# cont_board.net
KiCad netlist of a schematic drawn in EAGLE
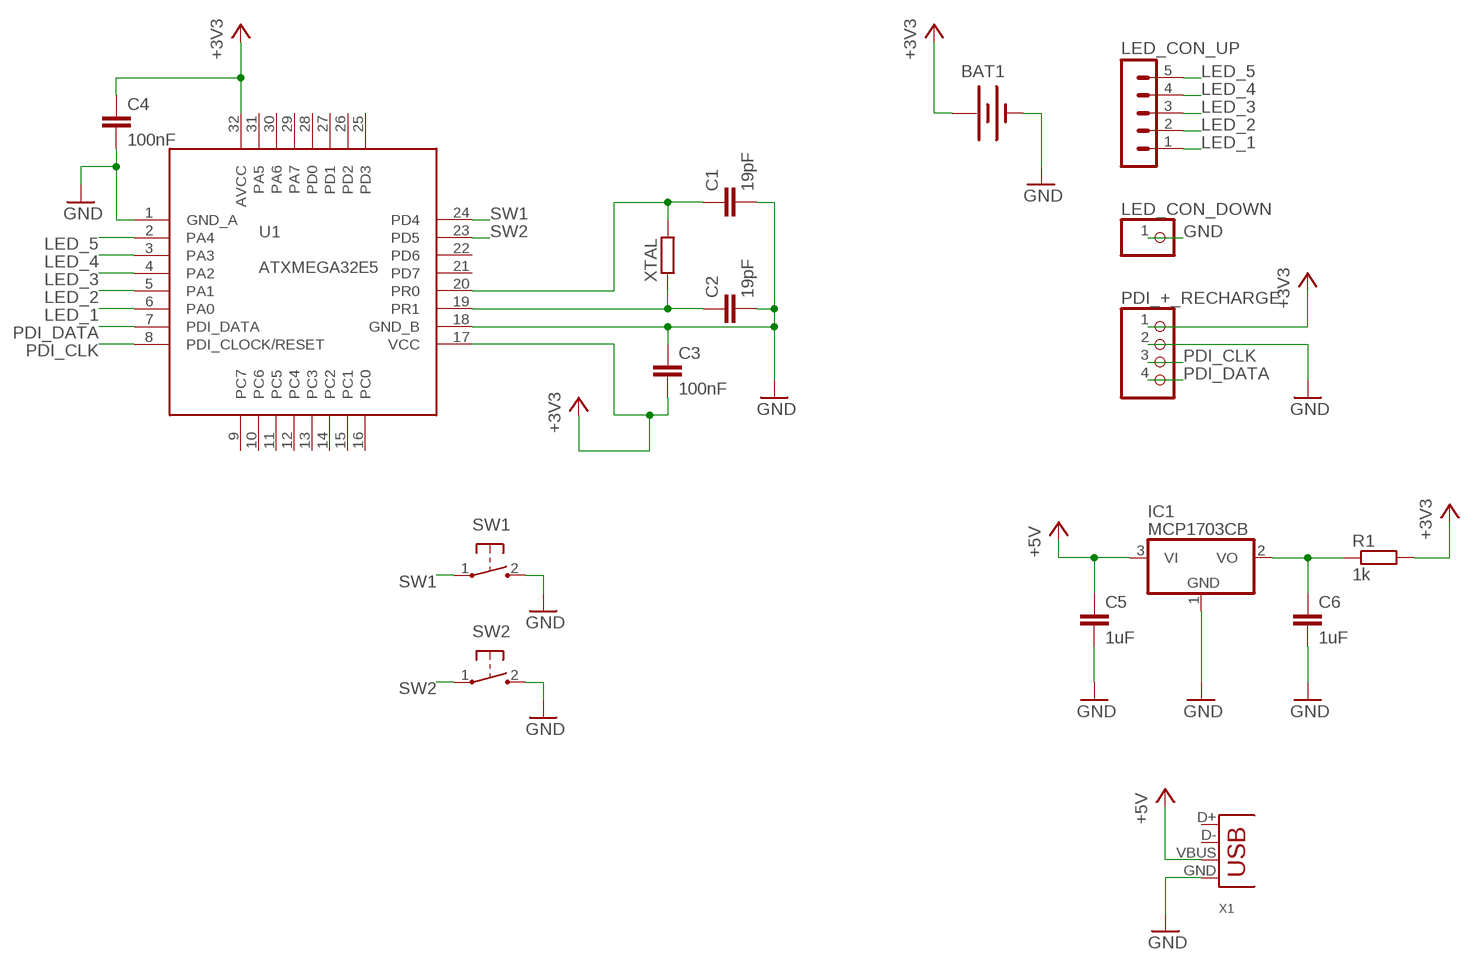
[diagram p0: schematic, sheet 1]

(export (version "E")
  (design (tool "Eeschema 10.0.6"))
  (components
    (comp (ref "BAT1")
      (value "BATTERY12MM")
      (footprint "eagle-import:BATTCON_12MM")
      (libsource (lib "eagle-import") (part "BATTERY12MM"))
    )
    (comp (ref "C1")
      (value "19pF")
      (footprint "eagle-import:C0402")
      (libsource (lib "eagle-import") (part "C-EUC0402"))
    )
    (comp (ref "C2")
      (value "19pF")
      (footprint "eagle-import:C0402")
      (libsource (lib "eagle-import") (part "C-EUC0402"))
    )
    (comp (ref "C3")
      (value "100nF")
      (footprint "eagle-import:C0402")
      (libsource (lib "eagle-import") (part "C-EUC0402"))
    )
    (comp (ref "C4")
      (value "100nF")
      (footprint "eagle-import:C0402")
      (libsource (lib "eagle-import") (part "C-EUC0402"))
    )
    (comp (ref "C5")
      (value "1uF")
      (footprint "eagle-import:C0402")
      (libsource (lib "eagle-import") (part "C-EUC0402"))
    )
    (comp (ref "C6")
      (value "1uF")
      (footprint "eagle-import:C0402")
      (libsource (lib "eagle-import") (part "C-EUC0402"))
    )
    (comp (ref "IC1")
      (value "MCP1703CB")
      (footprint "eagle-import:SOT23")
      (libsource (lib "eagle-import") (part "MCP1703CB"))
    )
    (comp (ref "LED_CON_DOWN")
      (value "PINHD-1X1")
      (footprint "eagle-import:1X01")
      (libsource (lib "eagle-import") (part "PINHD-1X1"))
    )
    (comp (ref "LED_CON_UP")
      (value "MA05-1")
      (footprint "eagle-import:MA05-1")
      (libsource (lib "eagle-import") (part "MA05-1"))
    )
    (comp (ref "PDI_+_RECHARGE")
      (value "PINHD-1X4")
      (footprint "eagle-import:1X04")
      (libsource (lib "eagle-import") (part "PINHD-1X4"))
    )
    (comp (ref "R1")
      (value "1k")
      (footprint "eagle-import:R0402")
      (libsource (lib "eagle-import") (part "R-EU_R0402"))
    )
    (comp (ref "SW1")
      (value "TAC_SWITCHSMD")
      (footprint "eagle-import:TACTILE-SWITCH-SMD")
      (libsource (lib "eagle-import") (part "TAC_SWITCHSMD"))
    )
    (comp (ref "SW2")
      (value "TAC_SWITCHSMD")
      (footprint "eagle-import:TACTILE-SWITCH-SMD")
      (libsource (lib "eagle-import") (part "TAC_SWITCHSMD"))
    )
    (comp (ref "U1")
      (value "ATXMEGA32E5")
      (footprint "eagle-import:TQFP32-08")
      (fields (field (name "MPN") "ATXMEGA32E5-AU"))
      (libsource (lib "eagle-import") (part "ATXMEGA32E5"))
    )
    (comp (ref "X1")
      (value "USBMICRO-B")
      (footprint "eagle-import:USB-MB-H")
      (libsource (lib "eagle-import") (part "USBMICRO-B"))
    )
    (comp (ref "XTAL")
      (value "R-EU_R0805")
      (footprint "eagle-import:R0805")
      (libsource (lib "eagle-import") (part "R-EU_R0805"))
    )
  )
  (nets
    (net (code "1") (name "+3V3") (class "Default")
      (node (ref "BAT1") (pin "PWR@1") (pinfunction "+_PWR@1") (pintype "power_in"))
      (node (ref "C3") (pin "2") (pinfunction "2_2") (pintype "passive"))
      (node (ref "C4") (pin "1") (pinfunction "1_1") (pintype "passive"))
      (node (ref "PDI_+_RECHARGE") (pin "1") (pinfunction "1_1") (pintype "passive"))
      (node (ref "R1") (pin "2") (pinfunction "2_2") (pintype "passive"))
      (node (ref "U1") (pin "17") (pinfunction "VCC_17") (pintype "power_in"))
      (node (ref "U1") (pin "32") (pinfunction "AVCC_32") (pintype "power_in"))
    )
    (net (code "2") (name "+5V") (class "Default")
      (node (ref "C5") (pin "1") (pinfunction "1_1") (pintype "passive"))
      (node (ref "IC1") (pin "3") (pinfunction "VI_3") (pintype "input"))
      (node (ref "X1") (pin "VBUS") (pinfunction "VBUS_VBUS") (pintype "bidirectional"))
    )
    (net (code "3") (name "/LED_1") (class "Default")
      (node (ref "LED_CON_UP") (pin "1") (pinfunction "1_1") (pintype "passive"))
      (node (ref "U1") (pin "6") (pinfunction "PA0_6") (pintype "bidirectional"))
    )
    (net (code "4") (name "/LED_2") (class "Default")
      (node (ref "LED_CON_UP") (pin "2") (pinfunction "2_2") (pintype "passive"))
      (node (ref "U1") (pin "5") (pinfunction "PA1_5") (pintype "bidirectional"))
    )
    (net (code "5") (name "/LED_3") (class "Default")
      (node (ref "LED_CON_UP") (pin "3") (pinfunction "3_3") (pintype "passive"))
      (node (ref "U1") (pin "4") (pinfunction "PA2_4") (pintype "bidirectional"))
    )
    (net (code "6") (name "/LED_4") (class "Default")
      (node (ref "LED_CON_UP") (pin "4") (pinfunction "4_4") (pintype "passive"))
      (node (ref "U1") (pin "3") (pinfunction "PA3_3") (pintype "bidirectional"))
    )
    (net (code "7") (name "/LED_5") (class "Default")
      (node (ref "LED_CON_UP") (pin "5") (pinfunction "5_5") (pintype "passive"))
      (node (ref "U1") (pin "2") (pinfunction "PA4_2") (pintype "bidirectional"))
    )
    (net (code "8") (name "/PDI_CLK") (class "Default")
      (node (ref "PDI_+_RECHARGE") (pin "3") (pinfunction "3_3") (pintype "passive"))
      (node (ref "U1") (pin "8") (pinfunction "PDI_CLOCK/RESET_8") (pintype "input"))
    )
    (net (code "9") (name "/PDI_DATA") (class "Default")
      (node (ref "PDI_+_RECHARGE") (pin "4") (pinfunction "4_4") (pintype "passive"))
      (node (ref "U1") (pin "7") (pinfunction "PDI_DATA_7") (pintype "input"))
    )
    (net (code "10") (name "/SW1") (class "Default")
      (node (ref "SW1") (pin "1") (pinfunction "1_1") (pintype "passive"))
      (node (ref "U1") (pin "24") (pinfunction "PD4_24") (pintype "bidirectional"))
    )
    (net (code "11") (name "/SW2") (class "Default")
      (node (ref "SW2") (pin "1") (pinfunction "1_1") (pintype "passive"))
      (node (ref "U1") (pin "23") (pinfunction "PD5_23") (pintype "bidirectional"))
    )
    (net (code "12") (name "GND") (class "Default")
      (node (ref "BAT1") (pin "GND") (pinfunction "-_GND") (pintype "power_in"))
      (node (ref "C1") (pin "2") (pinfunction "2_2") (pintype "passive"))
      (node (ref "C2") (pin "2") (pinfunction "2_2") (pintype "passive"))
      (node (ref "C3") (pin "1") (pinfunction "1_1") (pintype "passive"))
      (node (ref "C4") (pin "2") (pinfunction "2_2") (pintype "passive"))
      (node (ref "C5") (pin "2") (pinfunction "2_2") (pintype "passive"))
      (node (ref "C6") (pin "2") (pinfunction "2_2") (pintype "passive"))
      (node (ref "IC1") (pin "1") (pinfunction "GND_1") (pintype "passive"))
      (node (ref "LED_CON_DOWN") (pin "1") (pinfunction "1_1") (pintype "passive"))
      (node (ref "PDI_+_RECHARGE") (pin "2") (pinfunction "2_2") (pintype "passive"))
      (node (ref "SW1") (pin "2") (pinfunction "3_2") (pintype "passive"))
      (node (ref "SW2") (pin "2") (pinfunction "3_2") (pintype "passive"))
      (node (ref "U1") (pin "1") (pinfunction "GND_A_1") (pintype "passive"))
      (node (ref "U1") (pin "18") (pinfunction "GND_B_18") (pintype "passive"))
      (node (ref "X1") (pin "GND") (pinfunction "GND_GND") (pintype "bidirectional"))
    )
    (net (code "13") (name "Net-(IC1-VO)") (class "Default")
      (node (ref "C6") (pin "1") (pinfunction "1_1") (pintype "passive"))
      (node (ref "IC1") (pin "2") (pinfunction "VO_2") (pintype "passive"))
      (node (ref "R1") (pin "1") (pinfunction "1_1") (pintype "passive"))
    )
    (net (code "14") (name "Net-(U1-PR0)") (class "Default")
      (node (ref "C1") (pin "1") (pinfunction "1_1") (pintype "passive"))
      (node (ref "U1") (pin "20") (pinfunction "PR0_20") (pintype "input"))
      (node (ref "XTAL") (pin "2") (pinfunction "2_2") (pintype "passive"))
    )
    (net (code "15") (name "Net-(U1-PR1)") (class "Default")
      (node (ref "C2") (pin "1") (pinfunction "1_1") (pintype "passive"))
      (node (ref "U1") (pin "19") (pinfunction "PR1_19") (pintype "input"))
      (node (ref "XTAL") (pin "1") (pinfunction "1_1") (pintype "passive"))
    )
    (net (code "16") (name "unconnected-(U1-PA5-Pad31)") (class "Default")
      (node (ref "U1") (pin "31") (pinfunction "PA5_31") (pintype "bidirectional"))
    )
    (net (code "17") (name "unconnected-(U1-PA6-Pad30)") (class "Default")
      (node (ref "U1") (pin "30") (pinfunction "PA6_30") (pintype "bidirectional"))
    )
    (net (code "18") (name "unconnected-(U1-PA7-Pad29)") (class "Default")
      (node (ref "U1") (pin "29") (pinfunction "PA7_29") (pintype "bidirectional"))
    )
    (net (code "19") (name "unconnected-(U1-PC0-Pad16)") (class "Default")
      (node (ref "U1") (pin "16") (pinfunction "PC0_16") (pintype "bidirectional"))
    )
    (net (code "20") (name "unconnected-(U1-PC1-Pad15)") (class "Default")
      (node (ref "U1") (pin "15") (pinfunction "PC1_15") (pintype "bidirectional"))
    )
    (net (code "21") (name "unconnected-(U1-PC2-Pad14)") (class "Default")
      (node (ref "U1") (pin "14") (pinfunction "PC2_14") (pintype "bidirectional"))
    )
    (net (code "22") (name "unconnected-(U1-PC3-Pad13)") (class "Default")
      (node (ref "U1") (pin "13") (pinfunction "PC3_13") (pintype "bidirectional"))
    )
    (net (code "23") (name "unconnected-(U1-PC4-Pad12)") (class "Default")
      (node (ref "U1") (pin "12") (pinfunction "PC4_12") (pintype "bidirectional"))
    )
    (net (code "24") (name "unconnected-(U1-PC5-Pad11)") (class "Default")
      (node (ref "U1") (pin "11") (pinfunction "PC5_11") (pintype "bidirectional"))
    )
    (net (code "25") (name "unconnected-(U1-PC6-Pad10)") (class "Default")
      (node (ref "U1") (pin "10") (pinfunction "PC6_10") (pintype "bidirectional"))
    )
    (net (code "26") (name "unconnected-(U1-PC7-Pad9)") (class "Default")
      (node (ref "U1") (pin "9") (pinfunction "PC7_9") (pintype "bidirectional"))
    )
    (net (code "27") (name "unconnected-(U1-PD0-Pad28)") (class "Default")
      (node (ref "U1") (pin "28") (pinfunction "PD0_28") (pintype "bidirectional"))
    )
    (net (code "28") (name "unconnected-(U1-PD1-Pad27)") (class "Default")
      (node (ref "U1") (pin "27") (pinfunction "PD1_27") (pintype "bidirectional"))
    )
    (net (code "29") (name "unconnected-(U1-PD2-Pad26)") (class "Default")
      (node (ref "U1") (pin "26") (pinfunction "PD2_26") (pintype "bidirectional"))
    )
    (net (code "30") (name "unconnected-(U1-PD3-Pad25)") (class "Default")
      (node (ref "U1") (pin "25") (pinfunction "PD3_25") (pintype "bidirectional"))
    )
    (net (code "31") (name "unconnected-(U1-PD6-Pad22)") (class "Default")
      (node (ref "U1") (pin "22") (pinfunction "PD6_22") (pintype "bidirectional"))
    )
    (net (code "32") (name "unconnected-(U1-PD7-Pad21)") (class "Default")
      (node (ref "U1") (pin "21") (pinfunction "PD7_21") (pintype "bidirectional"))
    )
    (net (code "33") (name "unconnected-(X1-PadD+)") (class "Default")
      (node (ref "X1") (pin "D+") (pinfunction "D+_D+") (pintype "bidirectional"))
    )
    (net (code "34") (name "unconnected-(X1-PadD-)") (class "Default")
      (node (ref "X1") (pin "D-") (pinfunction "D-_D-") (pintype "bidirectional"))
    )
  )
)
